# STM32WB.net
KiCad netlist of a schematic drawn in Altium Designer
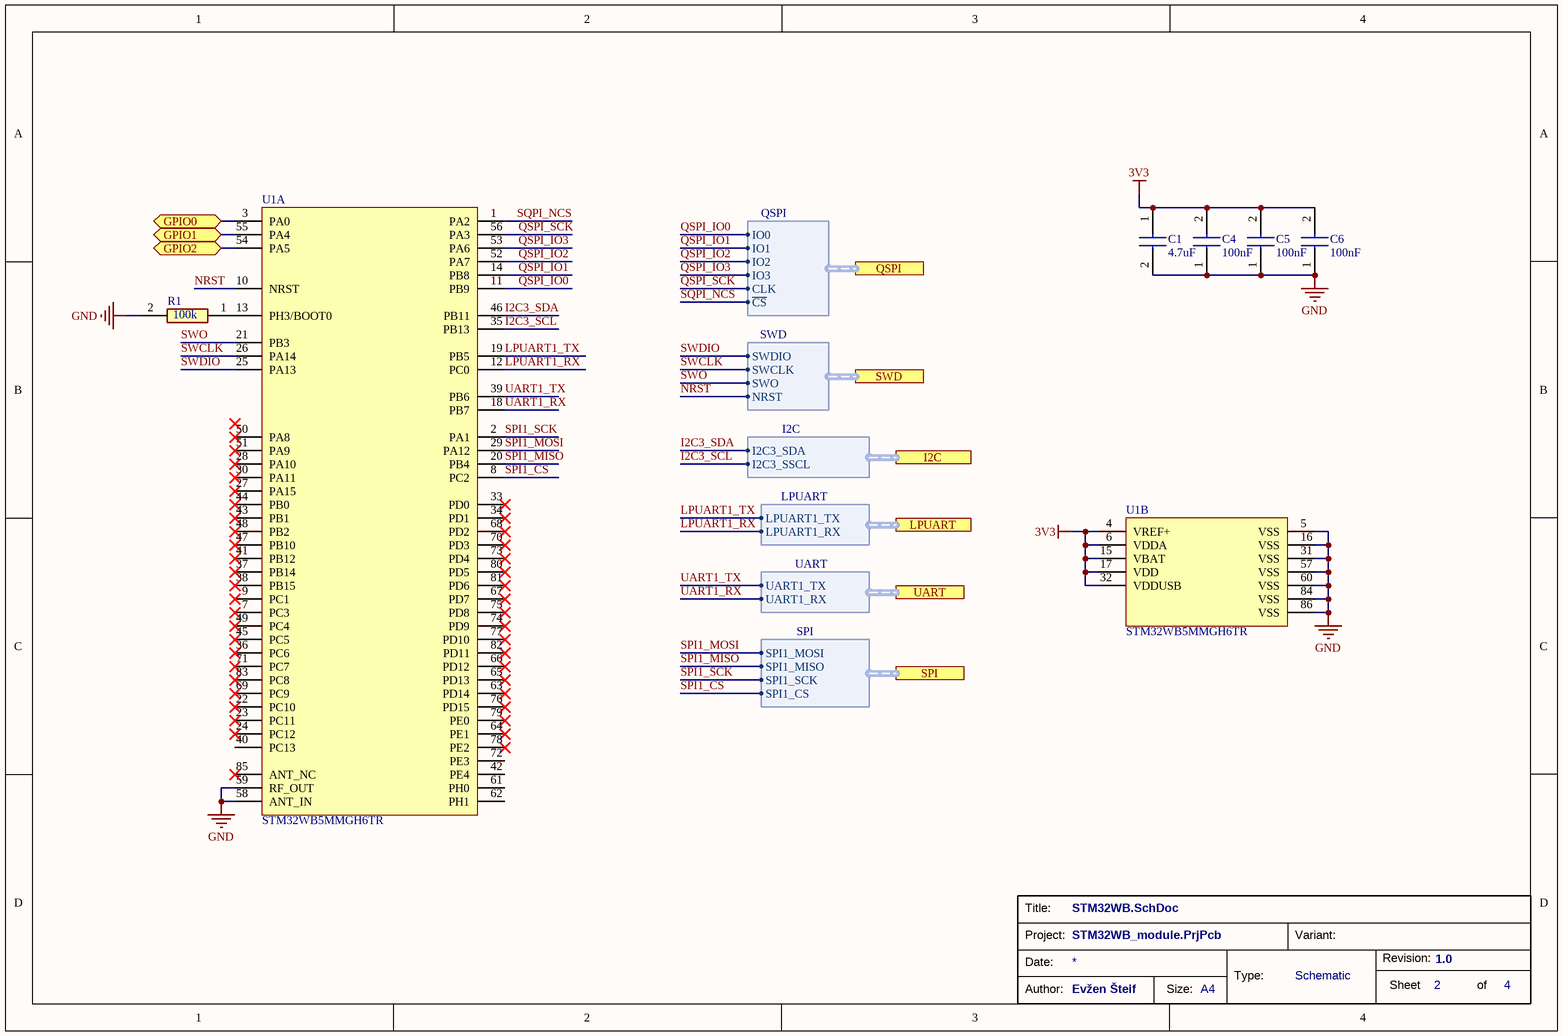
[diagram p0: STM32WB.SchDoc]

(export (version "E")
  (design (tool "Eeschema 10.0.6"))
  (components
    (comp (ref "C1")
      (value "4.7uF")
      (footprint "SamacSys:CAPC1608X90N")
      (description "Capacitor")
      (fields
        (field (name "MANUFACTURER_PART_NUMBER") "GRM188R61E475KE11J")
        (field (name "MOUSER PART NUMBER") "81-GRM188R61E475KE1J")
      )
      (libsource (lib "*") (part "GRM188R61E475KE11J"))
    )
    (comp (ref "C4")
      (value "100nF")
      (footprint "SamacSys:CAPC1005X70N")
      (description "Capacitor")
      (fields
        (field (name "MANUFACTURER_PART_NUMBER") "GRM155R61A104KA01D")
        (field (name "MOUSER PART NUMBER") "81-GRM155R61A104KA01")
      )
      (libsource (lib "*") (part "GRM155R61A104KA01D"))
    )
    (comp (ref "C5")
      (value "100nF")
      (footprint "SamacSys:CAPC1005X70N")
      (description "Capacitor")
      (fields
        (field (name "MANUFACTURER_PART_NUMBER") "GRM155R61A104KA01D")
        (field (name "MOUSER PART NUMBER") "81-GRM155R61A104KA01")
      )
      (libsource (lib "*") (part "GRM155R61A104KA01D"))
    )
    (comp (ref "C6")
      (value "100nF")
      (footprint "SamacSys:CAPC1005X70N")
      (description "Capacitor")
      (fields
        (field (name "MANUFACTURER_PART_NUMBER") "GRM155R61A104KA01D")
        (field (name "MOUSER PART NUMBER") "81-GRM155R61A104KA01")
      )
      (libsource (lib "*") (part "GRM155R61A104KA01D"))
    )
    (comp (ref "R1")
      (value "100k")
      (footprint "SamacSys:RESC1005X35N")
      (description "Resistor")
      (fields
        (field (name "MANUFACTURER_PART_NUMBER") "RT0402FRE07100KL")
        (field (name "MOUSER PART NUMBER") "603-RT0402FRE07100KL")
      )
      (libsource (lib "*") (part "RT0402FRE07100KL"))
    )
    (comp (ref "U1")
      (value "STM32WB5MMGH6TR")
      (footprint "MOD_DORY_STM_86P_7P3X11_H1P342_Ref2")
      (description "MCU module, LGA-86, Cortex-M4, 64 MHz, 1 MB Flash, 256 kB RAM, BLE 5.4, 802.15.4")
      (fields (field (name "MANUFACTURER") "STMicroelectronics"))
      (libsource (lib "SamacSys") (part "STM32WB5MMGH6TR"))
    )
  )
  (nets
    (net (code "7") (name "/GPIO0") (class "Default")
      (node (ref "U1") (pin "3") (pinfunction "PA0_3") (pintype "passive"))
    )
    (net (code "8") (name "/GPIO1") (class "Default")
      (node (ref "U1") (pin "55") (pinfunction "PA4_55") (pintype "passive"))
    )
    (net (code "9") (name "/GPIO2") (class "Default")
      (node (ref "U1") (pin "54") (pinfunction "PA5_54") (pintype "passive"))
    )
    (net (code "10") (name "/I2C3_SCL") (class "Default")
      (node (ref "U1") (pin "35") (pinfunction "PB13_35") (pintype "passive"))
    )
    (net (code "11") (name "/I2C3_SDA") (class "Default")
      (node (ref "U1") (pin "46") (pinfunction "PB11_46") (pintype "passive"))
    )
    (net (code "12") (name "/LPUART1_RX") (class "Default")
      (node (ref "U1") (pin "12") (pinfunction "PC0_12") (pintype "passive"))
    )
    (net (code "13") (name "/LPUART1_TX") (class "Default")
      (node (ref "U1") (pin "19") (pinfunction "PB5_19") (pintype "passive"))
    )
    (net (code "14") (name "/NRST") (class "Default")
      (node (ref "U1") (pin "10") (pinfunction "NRST_10") (pintype "passive"))
    )
    (net (code "15") (name "/QSPI_IO0") (class "Default")
      (node (ref "U1") (pin "11") (pinfunction "PB9_11") (pintype "passive"))
    )
    (net (code "16") (name "/QSPI_IO1") (class "Default")
      (node (ref "U1") (pin "14") (pinfunction "PB8_14") (pintype "passive"))
    )
    (net (code "17") (name "/QSPI_IO2") (class "Default")
      (node (ref "U1") (pin "52") (pinfunction "PA7_52") (pintype "passive"))
    )
    (net (code "18") (name "/QSPI_IO3") (class "Default")
      (node (ref "U1") (pin "53") (pinfunction "PA6_53") (pintype "passive"))
    )
    (net (code "19") (name "/QSPI_SCK") (class "Default")
      (node (ref "U1") (pin "56") (pinfunction "PA3_56") (pintype "passive"))
    )
    (net (code "20") (name "/SPI1_CS") (class "Default")
      (node (ref "U1") (pin "8") (pinfunction "PC2_8") (pintype "passive"))
    )
    (net (code "21") (name "/SPI1_MISO") (class "Default")
      (node (ref "U1") (pin "20") (pinfunction "PB4_20") (pintype "passive"))
    )
    (net (code "22") (name "/SPI1_MOSI") (class "Default")
      (node (ref "U1") (pin "29") (pinfunction "PA12_29") (pintype "passive"))
    )
    (net (code "23") (name "/SPI1_SCK") (class "Default")
      (node (ref "U1") (pin "2") (pinfunction "PA1_2") (pintype "passive"))
    )
    (net (code "24") (name "/SQPI_NCS") (class "Default")
      (node (ref "U1") (pin "1") (pinfunction "PA2_1") (pintype "passive"))
    )
    (net (code "25") (name "/SWCLK") (class "Default")
      (node (ref "U1") (pin "26") (pinfunction "PA14_26") (pintype "passive"))
    )
    (net (code "26") (name "/SWDIO") (class "Default")
      (node (ref "U1") (pin "25") (pinfunction "PA13_25") (pintype "passive"))
    )
    (net (code "27") (name "/SWO") (class "Default")
      (node (ref "U1") (pin "21") (pinfunction "PB3_21") (pintype "passive"))
    )
    (net (code "28") (name "/UART1_RX") (class "Default")
      (node (ref "U1") (pin "18") (pinfunction "PB7_18") (pintype "passive"))
    )
    (net (code "29") (name "/UART1_TX") (class "Default")
      (node (ref "U1") (pin "39") (pinfunction "PB6_39") (pintype "passive"))
    )
    (net (code "36") (name "3V3") (class "Default")
      (node (ref "C1") (pin "1") (pinfunction "1_1") (pintype "passive"))
      (node (ref "C4") (pin "2") (pinfunction "2_2") (pintype "passive"))
      (node (ref "C5") (pin "2") (pinfunction "2_2") (pintype "passive"))
      (node (ref "C6") (pin "2") (pinfunction "2_2") (pintype "passive"))
      (node (ref "U1") (pin "15") (pinfunction "VBAT_15") (pintype "passive"))
      (node (ref "U1") (pin "17") (pinfunction "VDD_17") (pintype "passive"))
      (node (ref "U1") (pin "32") (pinfunction "VDDUSB_32") (pintype "passive"))
      (node (ref "U1") (pin "4") (pinfunction "VREF+_4") (pintype "passive"))
      (node (ref "U1") (pin "6") (pinfunction "VDDA_6") (pintype "passive"))
    )
    (net (code "37") (name "GND") (class "Default")
      (node (ref "C1") (pin "2") (pinfunction "2_2") (pintype "passive"))
      (node (ref "C4") (pin "1") (pinfunction "1_1") (pintype "passive"))
      (node (ref "C5") (pin "1") (pinfunction "1_1") (pintype "passive"))
      (node (ref "C6") (pin "1") (pinfunction "1_1") (pintype "passive"))
      (node (ref "R1") (pin "2") (pinfunction "2_2") (pintype "passive"))
      (node (ref "U1") (pin "16") (pinfunction "VSS_16") (pintype "passive"))
      (node (ref "U1") (pin "31") (pinfunction "VSS_31") (pintype "passive"))
      (node (ref "U1") (pin "5") (pinfunction "VSS_5") (pintype "passive"))
      (node (ref "U1") (pin "57") (pinfunction "VSS_57") (pintype "passive"))
      (node (ref "U1") (pin "58") (pinfunction "ANT_IN_58") (pintype "passive"))
      (node (ref "U1") (pin "59") (pinfunction "RF_OUT_59") (pintype "passive"))
      (node (ref "U1") (pin "60") (pinfunction "VSS_60") (pintype "passive"))
      (node (ref "U1") (pin "84") (pinfunction "VSS_84") (pintype "passive"))
      (node (ref "U1") (pin "86") (pinfunction "VSS_86") (pintype "passive"))
    )
    (net (code "38") (name "Net-(U1A-PH3{slash}BOOT0)") (class "Default")
      (node (ref "R1") (pin "1") (pinfunction "1_1") (pintype "passive"))
      (node (ref "U1") (pin "13") (pinfunction "PH3/BOOT0_13") (pintype "passive"))
    )
    (net (code "39") (name "unconnected-(U1A-ANT_NC-Pad85)") (class "Default")
      (node (ref "U1") (pin "85") (pinfunction "ANT_NC_85") (pintype "passive+no_connect"))
    )
    (net (code "40") (name "unconnected-(U1A-PA8-Pad50)") (class "Default")
      (node (ref "U1") (pin "50") (pinfunction "PA8_50") (pintype "passive+no_connect"))
    )
    (net (code "41") (name "unconnected-(U1A-PA9-Pad51)") (class "Default")
      (node (ref "U1") (pin "51") (pinfunction "PA9_51") (pintype "passive+no_connect"))
    )
    (net (code "42") (name "unconnected-(U1A-PA10-Pad28)") (class "Default")
      (node (ref "U1") (pin "28") (pinfunction "PA10_28") (pintype "passive+no_connect"))
    )
    (net (code "43") (name "unconnected-(U1A-PA11-Pad30)") (class "Default")
      (node (ref "U1") (pin "30") (pinfunction "PA11_30") (pintype "passive+no_connect"))
    )
    (net (code "44") (name "unconnected-(U1A-PA15-Pad27)") (class "Default")
      (node (ref "U1") (pin "27") (pinfunction "PA15_27") (pintype "passive+no_connect"))
    )
    (net (code "45") (name "unconnected-(U1A-PB0-Pad44)") (class "Default")
      (node (ref "U1") (pin "44") (pinfunction "PB0_44") (pintype "passive+no_connect"))
    )
    (net (code "46") (name "unconnected-(U1A-PB1-Pad43)") (class "Default")
      (node (ref "U1") (pin "43") (pinfunction "PB1_43") (pintype "passive+no_connect"))
    )
    (net (code "47") (name "unconnected-(U1A-PB2-Pad48)") (class "Default")
      (node (ref "U1") (pin "48") (pinfunction "PB2_48") (pintype "passive+no_connect"))
    )
    (net (code "48") (name "unconnected-(U1A-PB10-Pad47)") (class "Default")
      (node (ref "U1") (pin "47") (pinfunction "PB10_47") (pintype "passive+no_connect"))
    )
    (net (code "49") (name "unconnected-(U1A-PB12-Pad41)") (class "Default")
      (node (ref "U1") (pin "41") (pinfunction "PB12_41") (pintype "passive+no_connect"))
    )
    (net (code "50") (name "unconnected-(U1A-PB14-Pad37)") (class "Default")
      (node (ref "U1") (pin "37") (pinfunction "PB14_37") (pintype "passive+no_connect"))
    )
    (net (code "51") (name "unconnected-(U1A-PB15-Pad38)") (class "Default")
      (node (ref "U1") (pin "38") (pinfunction "PB15_38") (pintype "passive+no_connect"))
    )
    (net (code "52") (name "unconnected-(U1A-PC1-Pad9)") (class "Default")
      (node (ref "U1") (pin "9") (pinfunction "PC1_9") (pintype "passive+no_connect"))
    )
    (net (code "53") (name "unconnected-(U1A-PC3-Pad7)") (class "Default")
      (node (ref "U1") (pin "7") (pinfunction "PC3_7") (pintype "passive+no_connect"))
    )
    (net (code "54") (name "unconnected-(U1A-PC4-Pad49)") (class "Default")
      (node (ref "U1") (pin "49") (pinfunction "PC4_49") (pintype "passive+no_connect"))
    )
    (net (code "55") (name "unconnected-(U1A-PC5-Pad45)") (class "Default")
      (node (ref "U1") (pin "45") (pinfunction "PC5_45") (pintype "passive+no_connect"))
    )
    (net (code "56") (name "unconnected-(U1A-PC6-Pad36)") (class "Default")
      (node (ref "U1") (pin "36") (pinfunction "PC6_36") (pintype "passive+no_connect"))
    )
    (net (code "57") (name "unconnected-(U1A-PC7-Pad71)") (class "Default")
      (node (ref "U1") (pin "71") (pinfunction "PC7_71") (pintype "passive+no_connect"))
    )
    (net (code "58") (name "unconnected-(U1A-PC8-Pad83)") (class "Default")
      (node (ref "U1") (pin "83") (pinfunction "PC8_83") (pintype "passive+no_connect"))
    )
    (net (code "59") (name "unconnected-(U1A-PC9-Pad69)") (class "Default")
      (node (ref "U1") (pin "69") (pinfunction "PC9_69") (pintype "passive+no_connect"))
    )
    (net (code "60") (name "unconnected-(U1A-PC10-Pad22)") (class "Default")
      (node (ref "U1") (pin "22") (pinfunction "PC10_22") (pintype "passive+no_connect"))
    )
    (net (code "61") (name "unconnected-(U1A-PC11-Pad23)") (class "Default")
      (node (ref "U1") (pin "23") (pinfunction "PC11_23") (pintype "passive+no_connect"))
    )
    (net (code "62") (name "unconnected-(U1A-PC12-Pad24)") (class "Default")
      (node (ref "U1") (pin "24") (pinfunction "PC12_24") (pintype "passive+no_connect"))
    )
    (net (code "63") (name "unconnected-(U1A-PC13-Pad40)") (class "Default")
      (node (ref "U1") (pin "40") (pinfunction "PC13_40") (pintype "passive"))
    )
    (net (code "64") (name "unconnected-(U1A-PD0-Pad33)") (class "Default")
      (node (ref "U1") (pin "33") (pinfunction "PD0_33") (pintype "passive+no_connect"))
    )
    (net (code "65") (name "unconnected-(U1A-PD1-Pad34)") (class "Default")
      (node (ref "U1") (pin "34") (pinfunction "PD1_34") (pintype "passive+no_connect"))
    )
    (net (code "66") (name "unconnected-(U1A-PD2-Pad68)") (class "Default")
      (node (ref "U1") (pin "68") (pinfunction "PD2_68") (pintype "passive+no_connect"))
    )
    (net (code "67") (name "unconnected-(U1A-PD3-Pad70)") (class "Default")
      (node (ref "U1") (pin "70") (pinfunction "PD3_70") (pintype "passive+no_connect"))
    )
    (net (code "68") (name "unconnected-(U1A-PD4-Pad73)") (class "Default")
      (node (ref "U1") (pin "73") (pinfunction "PD4_73") (pintype "passive+no_connect"))
    )
    (net (code "69") (name "unconnected-(U1A-PD5-Pad80)") (class "Default")
      (node (ref "U1") (pin "80") (pinfunction "PD5_80") (pintype "passive+no_connect"))
    )
    (net (code "70") (name "unconnected-(U1A-PD6-Pad81)") (class "Default")
      (node (ref "U1") (pin "81") (pinfunction "PD6_81") (pintype "passive+no_connect"))
    )
    (net (code "71") (name "unconnected-(U1A-PD7-Pad67)") (class "Default")
      (node (ref "U1") (pin "67") (pinfunction "PD7_67") (pintype "passive+no_connect"))
    )
    (net (code "72") (name "unconnected-(U1A-PD8-Pad75)") (class "Default")
      (node (ref "U1") (pin "75") (pinfunction "PD8_75") (pintype "passive+no_connect"))
    )
    (net (code "73") (name "unconnected-(U1A-PD9-Pad74)") (class "Default")
      (node (ref "U1") (pin "74") (pinfunction "PD9_74") (pintype "passive+no_connect"))
    )
    (net (code "74") (name "unconnected-(U1A-PD10-Pad77)") (class "Default")
      (node (ref "U1") (pin "77") (pinfunction "PD10_77") (pintype "passive+no_connect"))
    )
    (net (code "75") (name "unconnected-(U1A-PD11-Pad82)") (class "Default")
      (node (ref "U1") (pin "82") (pinfunction "PD11_82") (pintype "passive+no_connect"))
    )
    (net (code "76") (name "unconnected-(U1A-PD12-Pad66)") (class "Default")
      (node (ref "U1") (pin "66") (pinfunction "PD12_66") (pintype "passive+no_connect"))
    )
    (net (code "77") (name "unconnected-(U1A-PD13-Pad65)") (class "Default")
      (node (ref "U1") (pin "65") (pinfunction "PD13_65") (pintype "passive+no_connect"))
    )
    (net (code "78") (name "unconnected-(U1A-PD14-Pad63)") (class "Default")
      (node (ref "U1") (pin "63") (pinfunction "PD14_63") (pintype "passive+no_connect"))
    )
    (net (code "79") (name "unconnected-(U1A-PD15-Pad76)") (class "Default")
      (node (ref "U1") (pin "76") (pinfunction "PD15_76") (pintype "passive+no_connect"))
    )
    (net (code "80") (name "unconnected-(U1A-PE0-Pad79)") (class "Default")
      (node (ref "U1") (pin "79") (pinfunction "PE0_79") (pintype "passive+no_connect"))
    )
    (net (code "81") (name "unconnected-(U1A-PE1-Pad64)") (class "Default")
      (node (ref "U1") (pin "64") (pinfunction "PE1_64") (pintype "passive+no_connect"))
    )
    (net (code "82") (name "unconnected-(U1A-PE2-Pad78)") (class "Default")
      (node (ref "U1") (pin "78") (pinfunction "PE2_78") (pintype "passive+no_connect"))
    )
    (net (code "83") (name "unconnected-(U1A-PE3-Pad72)") (class "Default")
      (node (ref "U1") (pin "72") (pinfunction "PE3_72") (pintype "passive"))
    )
    (net (code "84") (name "unconnected-(U1A-PE4-Pad42)") (class "Default")
      (node (ref "U1") (pin "42") (pinfunction "PE4_42") (pintype "passive"))
    )
    (net (code "85") (name "unconnected-(U1A-PH0-Pad61)") (class "Default")
      (node (ref "U1") (pin "61") (pinfunction "PH0_61") (pintype "passive"))
    )
    (net (code "86") (name "unconnected-(U1A-PH1-Pad62)") (class "Default")
      (node (ref "U1") (pin "62") (pinfunction "PH1_62") (pintype "passive"))
    )
  )
)
